# 19_SOLENOID_HB_2.net
KiCad netlist of a schematic drawn in Altium Designer
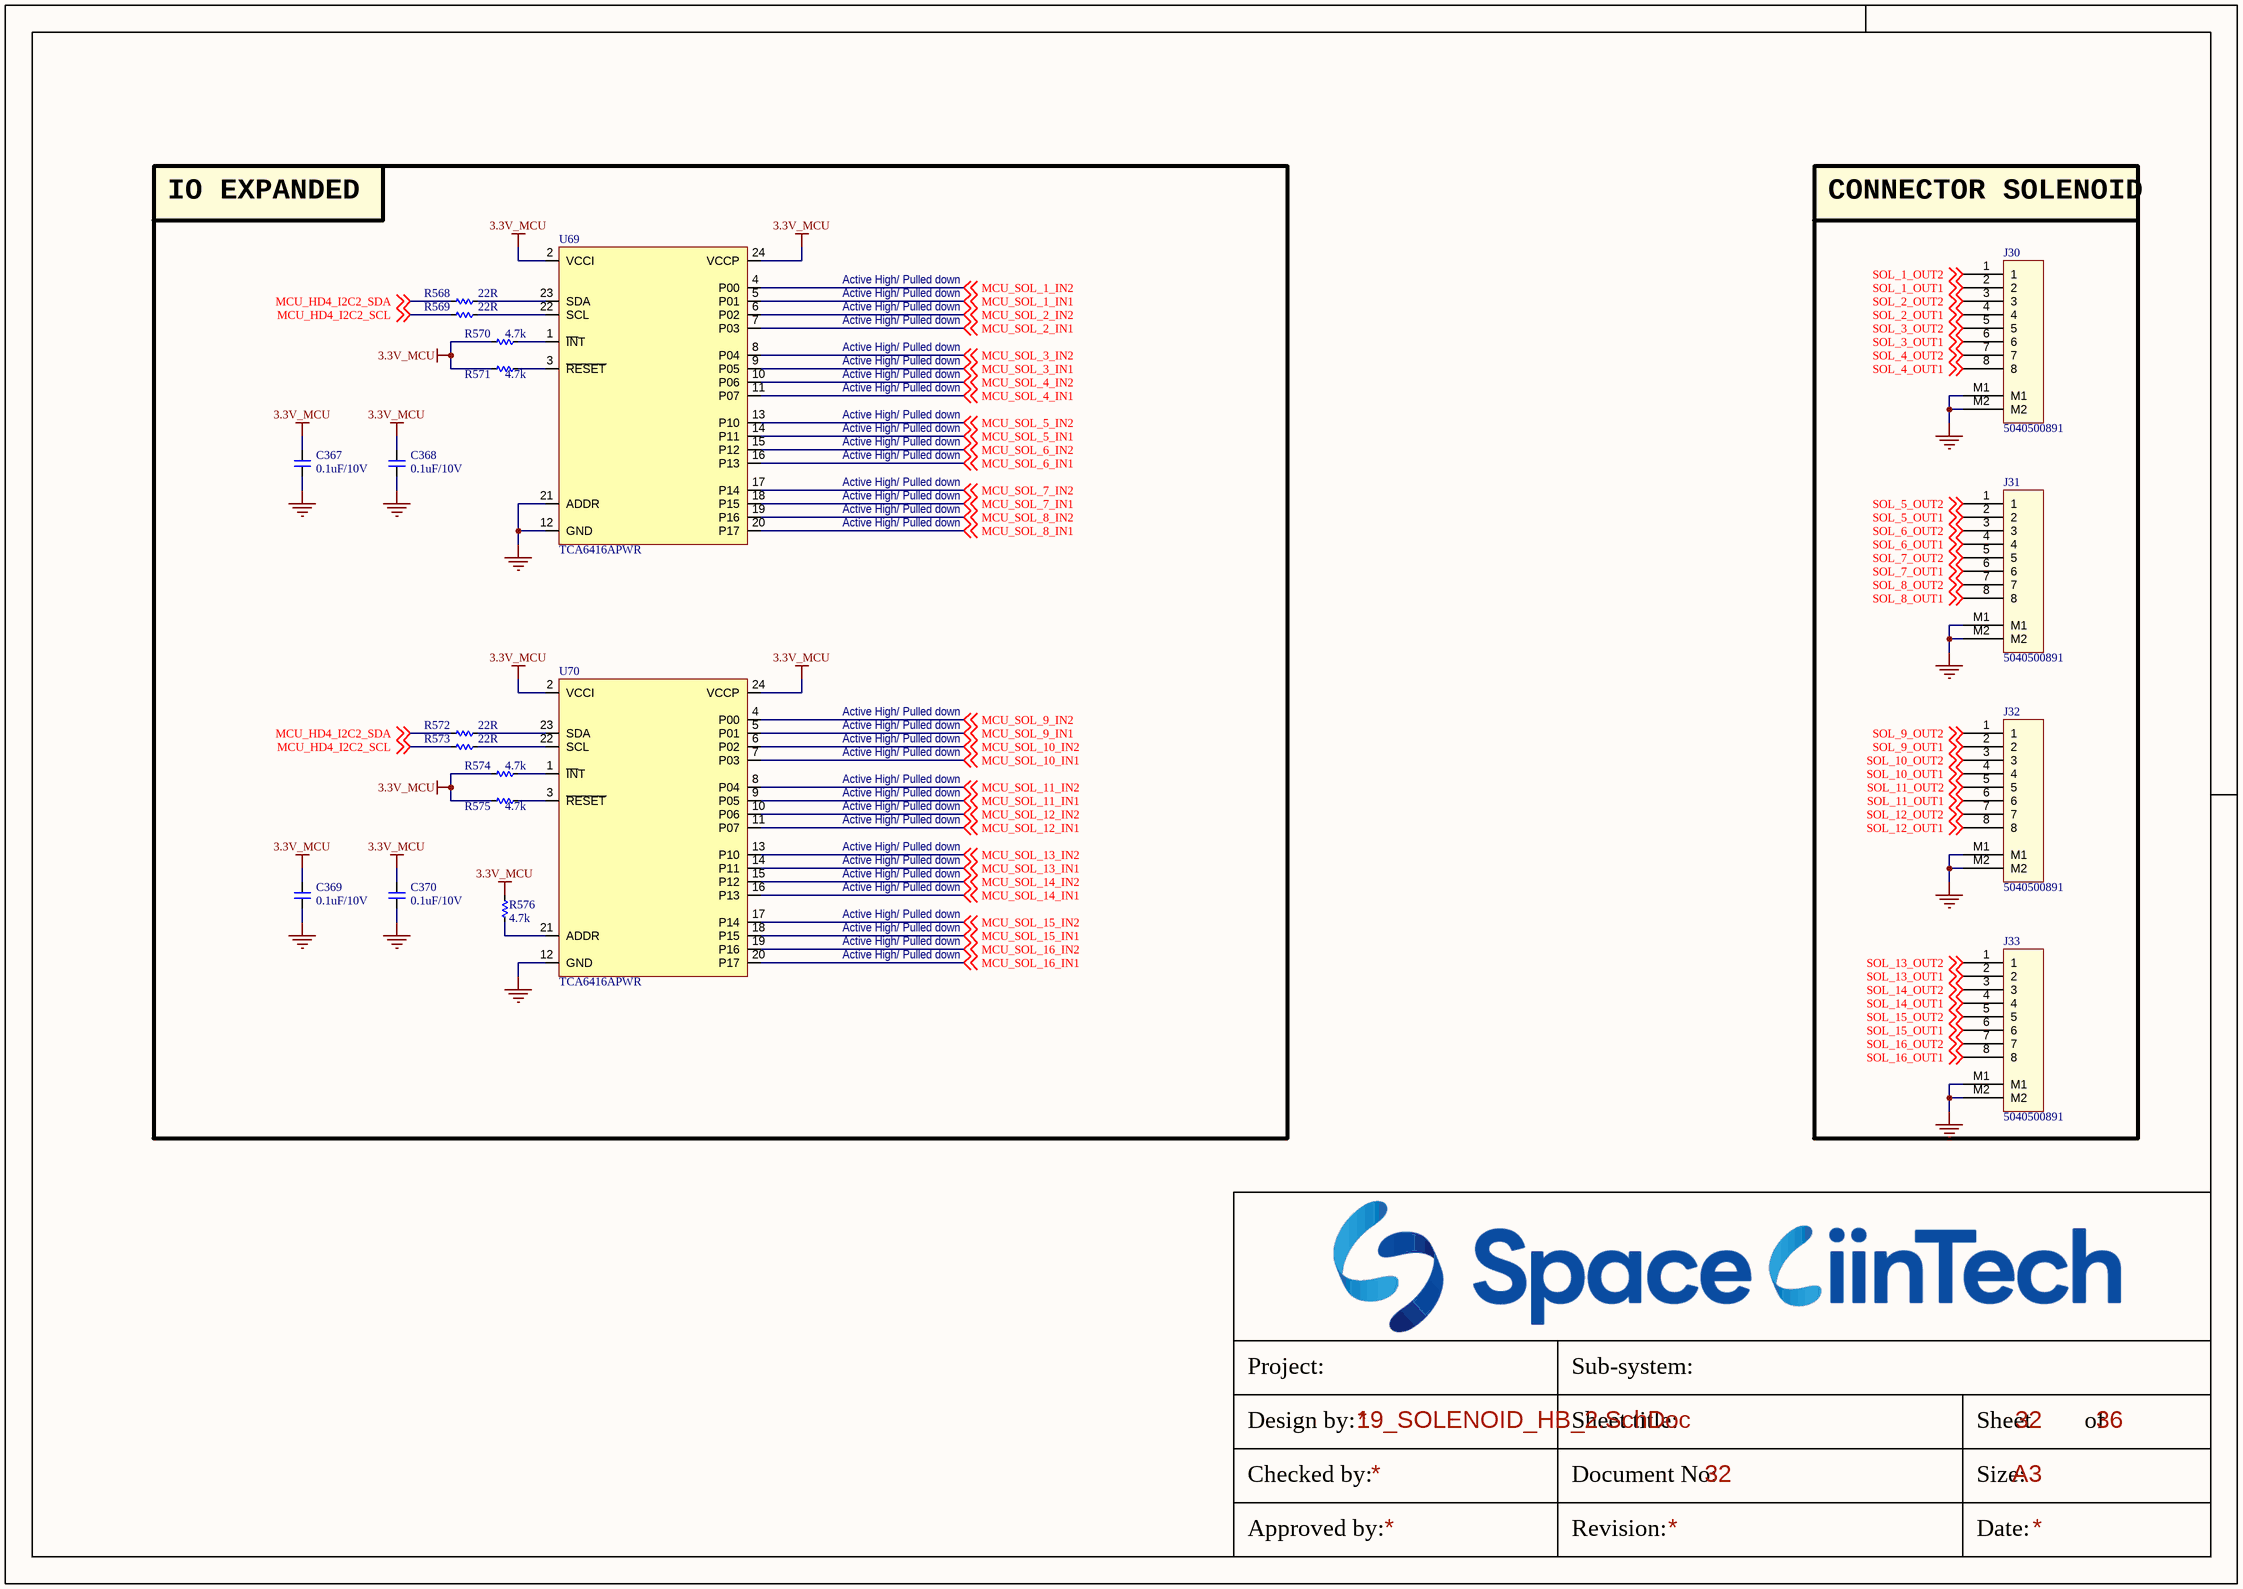
[diagram p0: 19_SOLENOID_HB_2.SchDoc]

(export (version "E")
  (design (tool "Eeschema 10.0.6"))
  (components
    (comp (ref "C367")
      (value "0.1uF/10V")
      (footprint "CAP_C_1005X50_L")
      (description "CAP")
      (libsource (lib "LABLIB") (part "_CAP_C_2"))
    )
    (comp (ref "C368")
      (value "0.1uF/10V")
      (footprint "CAP_C_1005X50_L")
      (description "CAP")
      (libsource (lib "LABLIB") (part "_CAP_C_2"))
    )
    (comp (ref "C369")
      (value "0.1uF/10V")
      (footprint "CAP_C_1005X50_L")
      (description "CAP")
      (libsource (lib "LABLIB") (part "_CAP_C_2"))
    )
    (comp (ref "C370")
      (value "0.1uF/10V")
      (footprint "CAP_C_1005X50_L")
      (description "CAP")
      (libsource (lib "LABLIB") (part "_CAP_C_2"))
    )
    (comp (ref "J30")
      (value "5040500891")
      (footprint "MOLEX_5040500891")
      (libsource (lib "LABLIB") (part "Header 8x1_2M"))
    )
    (comp (ref "J31")
      (value "5040500891")
      (footprint "MOLEX_5040500891")
      (libsource (lib "LABLIB") (part "Header 8x1_2M"))
    )
    (comp (ref "J32")
      (value "5040500891")
      (footprint "MOLEX_5040500891")
      (libsource (lib "LABLIB") (part "Header 8x1_2M"))
    )
    (comp (ref "J33")
      (value "5040500891")
      (footprint "MOLEX_5040500891")
      (libsource (lib "LABLIB") (part "Header 8x1_2M"))
    )
    (comp (ref "R568")
      (value "22R")
      (footprint "RES_C_1005x30_L")
      (description "RES")
      (libsource (lib "LABLIB") (part "_RES_B_2"))
    )
    (comp (ref "R569")
      (value "22R")
      (footprint "RES_C_1005x30_L")
      (description "RES")
      (libsource (lib "LABLIB") (part "_RES_B_2"))
    )
    (comp (ref "R570")
      (value "4.7k")
      (footprint "RES_C_1005x30_L")
      (description "RES")
      (libsource (lib "LABLIB") (part "_RES_B_2"))
    )
    (comp (ref "R571")
      (value "4.7k")
      (footprint "RES_C_1005x30_L")
      (description "RES")
      (libsource (lib "LABLIB") (part "_RES_B_2"))
    )
    (comp (ref "R572")
      (value "22R")
      (footprint "RES_C_1005x30_L")
      (description "RES")
      (libsource (lib "LABLIB") (part "_RES_B_2"))
    )
    (comp (ref "R573")
      (value "22R")
      (footprint "RES_C_1005x30_L")
      (description "RES")
      (libsource (lib "LABLIB") (part "_RES_B_2"))
    )
    (comp (ref "R574")
      (value "4.7k")
      (footprint "RES_C_1005x30_L")
      (description "RES")
      (libsource (lib "LABLIB") (part "_RES_B_2"))
    )
    (comp (ref "R575")
      (value "4.7k")
      (footprint "RES_C_1005x30_L")
      (description "RES")
      (libsource (lib "LABLIB") (part "_RES_B_2"))
    )
    (comp (ref "R576")
      (value "4.7k")
      (footprint "RES_C_1005x30_L")
      (description "RES")
      (libsource (lib "LABLIB") (part "_RES_B_2"))
    )
    (comp (ref "U69")
      (value "TCA6416APWR")
      (footprint "SOP65P440W-24N")
      (libsource (lib "CAMERA_SchLib") (part "IC_I2Cto16IO_TCA6416APWR"))
    )
    (comp (ref "U70")
      (value "TCA6416APWR")
      (footprint "SOP65P440W-24N")
      (libsource (lib "CAMERA_SchLib") (part "IC_I2Cto16IO_TCA6416APWR"))
    )
  )
  (nets
    (net (code "1") (name "3.3V_MCU") (class "Default")
      (node (ref "C367") (pin "2") (pinfunction "2_2") (pintype "passive"))
      (node (ref "C368") (pin "2") (pinfunction "2_2") (pintype "passive"))
      (node (ref "C369") (pin "2") (pinfunction "2_2") (pintype "passive"))
      (node (ref "C370") (pin "2") (pinfunction "2_2") (pintype "passive"))
      (node (ref "R570") (pin "1") (pinfunction "1_1") (pintype "passive"))
      (node (ref "R571") (pin "1") (pinfunction "1_1") (pintype "passive"))
      (node (ref "R574") (pin "1") (pinfunction "1_1") (pintype "passive"))
      (node (ref "R575") (pin "1") (pinfunction "1_1") (pintype "passive"))
      (node (ref "R576") (pin "2") (pinfunction "2_2") (pintype "passive"))
      (node (ref "U69") (pin "2") (pinfunction "VCCI_2") (pintype "passive"))
      (node (ref "U69") (pin "24") (pinfunction "VCCP_24") (pintype "passive"))
      (node (ref "U70") (pin "2") (pinfunction "VCCI_2") (pintype "passive"))
      (node (ref "U70") (pin "24") (pinfunction "VCCP_24") (pintype "passive"))
    )
    (net (code "2") (name "GND") (class "Default")
      (node (ref "C367") (pin "1") (pinfunction "1_1") (pintype "passive"))
      (node (ref "C368") (pin "1") (pinfunction "1_1") (pintype "passive"))
      (node (ref "C369") (pin "1") (pinfunction "1_1") (pintype "passive"))
      (node (ref "C370") (pin "1") (pinfunction "1_1") (pintype "passive"))
      (node (ref "J30") (pin "M1") (pinfunction "M1_M1") (pintype "passive"))
      (node (ref "J30") (pin "M2") (pinfunction "M2_M2") (pintype "passive"))
      (node (ref "J31") (pin "M1") (pinfunction "M1_M1") (pintype "passive"))
      (node (ref "J31") (pin "M2") (pinfunction "M2_M2") (pintype "passive"))
      (node (ref "J32") (pin "M1") (pinfunction "M1_M1") (pintype "passive"))
      (node (ref "J32") (pin "M2") (pinfunction "M2_M2") (pintype "passive"))
      (node (ref "J33") (pin "M1") (pinfunction "M1_M1") (pintype "passive"))
      (node (ref "J33") (pin "M2") (pinfunction "M2_M2") (pintype "passive"))
      (node (ref "U69") (pin "12") (pinfunction "GND_12") (pintype "passive"))
      (node (ref "U69") (pin "21") (pinfunction "ADDR_21") (pintype "passive"))
      (node (ref "U70") (pin "12") (pinfunction "GND_12") (pintype "passive"))
    )
    (net (code "3") (name "MCU_HD4_I2C2_SCL") (class "Default")
      (node (ref "R569") (pin "1") (pinfunction "1_1") (pintype "passive"))
      (node (ref "R573") (pin "1") (pinfunction "1_1") (pintype "passive"))
    )
    (net (code "4") (name "MCU_HD4_I2C2_SDA") (class "Default")
      (node (ref "R568") (pin "1") (pinfunction "1_1") (pintype "passive"))
      (node (ref "R572") (pin "1") (pinfunction "1_1") (pintype "passive"))
    )
    (net (code "5") (name "MCU_SOL_1_IN1") (class "Default")
      (node (ref "U69") (pin "5") (pinfunction "P01_5") (pintype "passive"))
    )
    (net (code "6") (name "MCU_SOL_1_IN2") (class "Default")
      (node (ref "U69") (pin "4") (pinfunction "P00_4") (pintype "passive"))
    )
    (net (code "7") (name "MCU_SOL_2_IN1") (class "Default")
      (node (ref "U69") (pin "7") (pinfunction "P03_7") (pintype "passive"))
    )
    (net (code "8") (name "MCU_SOL_2_IN2") (class "Default")
      (node (ref "U69") (pin "6") (pinfunction "P02_6") (pintype "passive"))
    )
    (net (code "9") (name "MCU_SOL_3_IN1") (class "Default")
      (node (ref "U69") (pin "9") (pinfunction "P05_9") (pintype "passive"))
    )
    (net (code "10") (name "MCU_SOL_3_IN2") (class "Default")
      (node (ref "U69") (pin "8") (pinfunction "P04_8") (pintype "passive"))
    )
    (net (code "11") (name "MCU_SOL_4_IN1") (class "Default")
      (node (ref "U69") (pin "11") (pinfunction "P07_11") (pintype "passive"))
    )
    (net (code "12") (name "MCU_SOL_4_IN2") (class "Default")
      (node (ref "U69") (pin "10") (pinfunction "P06_10") (pintype "passive"))
    )
    (net (code "13") (name "MCU_SOL_5_IN1") (class "Default")
      (node (ref "U69") (pin "14") (pinfunction "P11_14") (pintype "passive"))
    )
    (net (code "14") (name "MCU_SOL_5_IN2") (class "Default")
      (node (ref "U69") (pin "13") (pinfunction "P10_13") (pintype "passive"))
    )
    (net (code "15") (name "MCU_SOL_6_IN1") (class "Default")
      (node (ref "U69") (pin "16") (pinfunction "P13_16") (pintype "passive"))
    )
    (net (code "16") (name "MCU_SOL_6_IN2") (class "Default")
      (node (ref "U69") (pin "15") (pinfunction "P12_15") (pintype "passive"))
    )
    (net (code "17") (name "MCU_SOL_7_IN1") (class "Default")
      (node (ref "U69") (pin "18") (pinfunction "P15_18") (pintype "passive"))
    )
    (net (code "18") (name "MCU_SOL_7_IN2") (class "Default")
      (node (ref "U69") (pin "17") (pinfunction "P14_17") (pintype "passive"))
    )
    (net (code "19") (name "MCU_SOL_8_IN1") (class "Default")
      (node (ref "U69") (pin "20") (pinfunction "P17_20") (pintype "passive"))
    )
    (net (code "20") (name "MCU_SOL_8_IN2") (class "Default")
      (node (ref "U69") (pin "19") (pinfunction "P16_19") (pintype "passive"))
    )
    (net (code "21") (name "MCU_SOL_9_IN1") (class "Default")
      (node (ref "U70") (pin "5") (pinfunction "P01_5") (pintype "passive"))
    )
    (net (code "22") (name "MCU_SOL_9_IN2") (class "Default")
      (node (ref "U70") (pin "4") (pinfunction "P00_4") (pintype "passive"))
    )
    (net (code "23") (name "MCU_SOL_10_IN1") (class "Default")
      (node (ref "U70") (pin "7") (pinfunction "P03_7") (pintype "passive"))
    )
    (net (code "24") (name "MCU_SOL_10_IN2") (class "Default")
      (node (ref "U70") (pin "6") (pinfunction "P02_6") (pintype "passive"))
    )
    (net (code "25") (name "MCU_SOL_11_IN1") (class "Default")
      (node (ref "U70") (pin "9") (pinfunction "P05_9") (pintype "passive"))
    )
    (net (code "26") (name "MCU_SOL_11_IN2") (class "Default")
      (node (ref "U70") (pin "8") (pinfunction "P04_8") (pintype "passive"))
    )
    (net (code "27") (name "MCU_SOL_12_IN1") (class "Default")
      (node (ref "U70") (pin "11") (pinfunction "P07_11") (pintype "passive"))
    )
    (net (code "28") (name "MCU_SOL_12_IN2") (class "Default")
      (node (ref "U70") (pin "10") (pinfunction "P06_10") (pintype "passive"))
    )
    (net (code "29") (name "MCU_SOL_13_IN1") (class "Default")
      (node (ref "U70") (pin "14") (pinfunction "P11_14") (pintype "passive"))
    )
    (net (code "30") (name "MCU_SOL_13_IN2") (class "Default")
      (node (ref "U70") (pin "13") (pinfunction "P10_13") (pintype "passive"))
    )
    (net (code "31") (name "MCU_SOL_14_IN1") (class "Default")
      (node (ref "U70") (pin "16") (pinfunction "P13_16") (pintype "passive"))
    )
    (net (code "32") (name "MCU_SOL_14_IN2") (class "Default")
      (node (ref "U70") (pin "15") (pinfunction "P12_15") (pintype "passive"))
    )
    (net (code "33") (name "MCU_SOL_15_IN1") (class "Default")
      (node (ref "U70") (pin "18") (pinfunction "P15_18") (pintype "passive"))
    )
    (net (code "34") (name "MCU_SOL_15_IN2") (class "Default")
      (node (ref "U70") (pin "17") (pinfunction "P14_17") (pintype "passive"))
    )
    (net (code "35") (name "MCU_SOL_16_IN1") (class "Default")
      (node (ref "U70") (pin "20") (pinfunction "P17_20") (pintype "passive"))
    )
    (net (code "36") (name "MCU_SOL_16_IN2") (class "Default")
      (node (ref "U70") (pin "19") (pinfunction "P16_19") (pintype "passive"))
    )
    (net (code "37") (name "Net-(U69-SCL)") (class "Default")
      (node (ref "R569") (pin "2") (pinfunction "2_2") (pintype "passive"))
      (node (ref "U69") (pin "22") (pinfunction "SCL_22") (pintype "passive"))
    )
    (net (code "38") (name "Net-(U69-SDA)") (class "Default")
      (node (ref "R568") (pin "2") (pinfunction "2_2") (pintype "passive"))
      (node (ref "U69") (pin "23") (pinfunction "SDA_23") (pintype "passive"))
    )
    (net (code "39") (name "Net-(U69-~{IN}T)") (class "Default")
      (node (ref "R570") (pin "2") (pinfunction "2_2") (pintype "passive"))
      (node (ref "U69") (pin "1") (pinfunction "~{IN}T_1") (pintype "passive"))
    )
    (net (code "40") (name "Net-(U69-~{RESET})") (class "Default")
      (node (ref "R571") (pin "2") (pinfunction "2_2") (pintype "passive"))
      (node (ref "U69") (pin "3") (pinfunction "~{RESET}_3") (pintype "passive"))
    )
    (net (code "41") (name "Net-(U70-ADDR)") (class "Default")
      (node (ref "R576") (pin "1") (pinfunction "1_1") (pintype "passive"))
      (node (ref "U70") (pin "21") (pinfunction "ADDR_21") (pintype "passive"))
    )
    (net (code "42") (name "Net-(U70-SCL)") (class "Default")
      (node (ref "R573") (pin "2") (pinfunction "2_2") (pintype "passive"))
      (node (ref "U70") (pin "22") (pinfunction "SCL_22") (pintype "passive"))
    )
    (net (code "43") (name "Net-(U70-SDA)") (class "Default")
      (node (ref "R572") (pin "2") (pinfunction "2_2") (pintype "passive"))
      (node (ref "U70") (pin "23") (pinfunction "SDA_23") (pintype "passive"))
    )
    (net (code "44") (name "Net-(U70-~{IN}T)") (class "Default")
      (node (ref "R574") (pin "2") (pinfunction "2_2") (pintype "passive"))
      (node (ref "U70") (pin "1") (pinfunction "~{IN}T_1") (pintype "passive"))
    )
    (net (code "45") (name "Net-(U70-~{RESET})") (class "Default")
      (node (ref "R575") (pin "2") (pinfunction "2_2") (pintype "passive"))
      (node (ref "U70") (pin "3") (pinfunction "~{RESET}_3") (pintype "passive"))
    )
    (net (code "46") (name "SOL_1_OUT1") (class "Default")
      (node (ref "J30") (pin "2") (pinfunction "2_2") (pintype "passive"))
    )
    (net (code "47") (name "SOL_1_OUT2") (class "Default")
      (node (ref "J30") (pin "1") (pinfunction "1_1") (pintype "passive"))
    )
    (net (code "48") (name "SOL_2_OUT1") (class "Default")
      (node (ref "J30") (pin "4") (pinfunction "4_4") (pintype "passive"))
    )
    (net (code "49") (name "SOL_2_OUT2") (class "Default")
      (node (ref "J30") (pin "3") (pinfunction "3_3") (pintype "passive"))
    )
    (net (code "50") (name "SOL_3_OUT1") (class "Default")
      (node (ref "J30") (pin "6") (pinfunction "6_6") (pintype "passive"))
    )
    (net (code "51") (name "SOL_3_OUT2") (class "Default")
      (node (ref "J30") (pin "5") (pinfunction "5_5") (pintype "passive"))
    )
    (net (code "52") (name "SOL_4_OUT1") (class "Default")
      (node (ref "J30") (pin "8") (pinfunction "8_8") (pintype "passive"))
    )
    (net (code "53") (name "SOL_4_OUT2") (class "Default")
      (node (ref "J30") (pin "7") (pinfunction "7_7") (pintype "passive"))
    )
    (net (code "54") (name "SOL_5_OUT1") (class "Default")
      (node (ref "J31") (pin "2") (pinfunction "2_2") (pintype "passive"))
    )
    (net (code "55") (name "SOL_5_OUT2") (class "Default")
      (node (ref "J31") (pin "1") (pinfunction "1_1") (pintype "passive"))
    )
    (net (code "56") (name "SOL_6_OUT1") (class "Default")
      (node (ref "J31") (pin "4") (pinfunction "4_4") (pintype "passive"))
    )
    (net (code "57") (name "SOL_6_OUT2") (class "Default")
      (node (ref "J31") (pin "3") (pinfunction "3_3") (pintype "passive"))
    )
    (net (code "58") (name "SOL_7_OUT1") (class "Default")
      (node (ref "J31") (pin "6") (pinfunction "6_6") (pintype "passive"))
    )
    (net (code "59") (name "SOL_7_OUT2") (class "Default")
      (node (ref "J31") (pin "5") (pinfunction "5_5") (pintype "passive"))
    )
    (net (code "60") (name "SOL_8_OUT1") (class "Default")
      (node (ref "J31") (pin "8") (pinfunction "8_8") (pintype "passive"))
    )
    (net (code "61") (name "SOL_8_OUT2") (class "Default")
      (node (ref "J31") (pin "7") (pinfunction "7_7") (pintype "passive"))
    )
    (net (code "62") (name "SOL_9_OUT1") (class "Default")
      (node (ref "J32") (pin "2") (pinfunction "2_2") (pintype "passive"))
    )
    (net (code "63") (name "SOL_9_OUT2") (class "Default")
      (node (ref "J32") (pin "1") (pinfunction "1_1") (pintype "passive"))
    )
    (net (code "64") (name "SOL_10_OUT1") (class "Default")
      (node (ref "J32") (pin "4") (pinfunction "4_4") (pintype "passive"))
    )
    (net (code "65") (name "SOL_10_OUT2") (class "Default")
      (node (ref "J32") (pin "3") (pinfunction "3_3") (pintype "passive"))
    )
    (net (code "66") (name "SOL_11_OUT1") (class "Default")
      (node (ref "J32") (pin "6") (pinfunction "6_6") (pintype "passive"))
    )
    (net (code "67") (name "SOL_11_OUT2") (class "Default")
      (node (ref "J32") (pin "5") (pinfunction "5_5") (pintype "passive"))
    )
    (net (code "68") (name "SOL_12_OUT1") (class "Default")
      (node (ref "J32") (pin "8") (pinfunction "8_8") (pintype "passive"))
    )
    (net (code "69") (name "SOL_12_OUT2") (class "Default")
      (node (ref "J32") (pin "7") (pinfunction "7_7") (pintype "passive"))
    )
    (net (code "70") (name "SOL_13_OUT1") (class "Default")
      (node (ref "J33") (pin "2") (pinfunction "2_2") (pintype "passive"))
    )
    (net (code "71") (name "SOL_13_OUT2") (class "Default")
      (node (ref "J33") (pin "1") (pinfunction "1_1") (pintype "passive"))
    )
    (net (code "72") (name "SOL_14_OUT1") (class "Default")
      (node (ref "J33") (pin "4") (pinfunction "4_4") (pintype "passive"))
    )
    (net (code "73") (name "SOL_14_OUT2") (class "Default")
      (node (ref "J33") (pin "3") (pinfunction "3_3") (pintype "passive"))
    )
    (net (code "74") (name "SOL_15_OUT1") (class "Default")
      (node (ref "J33") (pin "6") (pinfunction "6_6") (pintype "passive"))
    )
    (net (code "75") (name "SOL_15_OUT2") (class "Default")
      (node (ref "J33") (pin "5") (pinfunction "5_5") (pintype "passive"))
    )
    (net (code "76") (name "SOL_16_OUT1") (class "Default")
      (node (ref "J33") (pin "8") (pinfunction "8_8") (pintype "passive"))
    )
    (net (code "77") (name "SOL_16_OUT2") (class "Default")
      (node (ref "J33") (pin "7") (pinfunction "7_7") (pintype "passive"))
    )
  )
)
